# Voltage_Regulation.net
KiCad netlist of a schematic drawn in Altium Designer
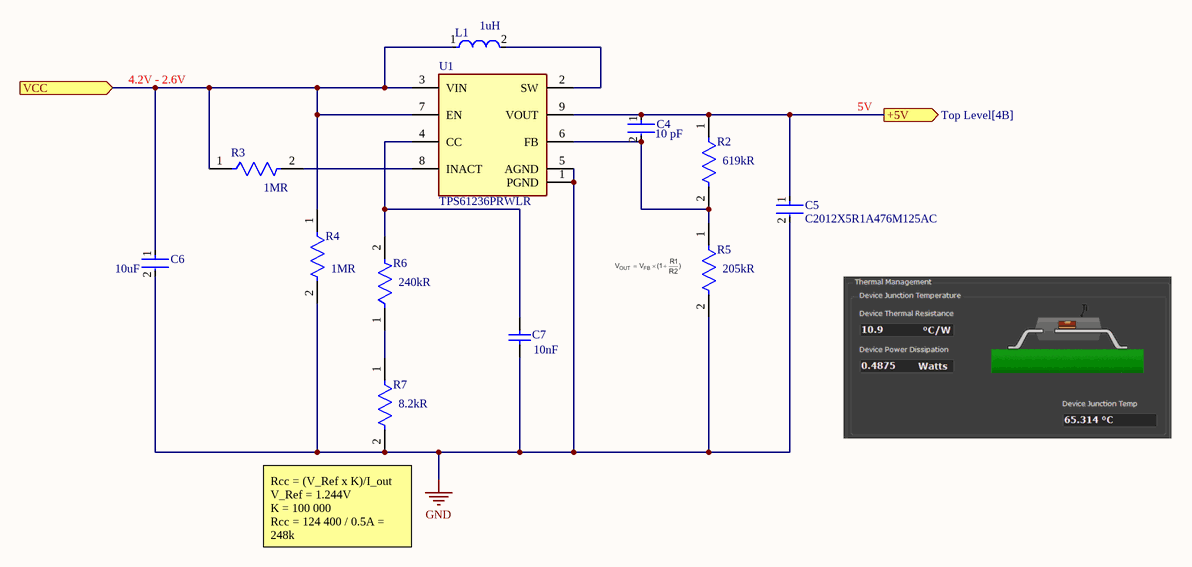
[diagram p0: Voltage Regulation.SchDoc]

(export (version "E")
  (design (tool "Eeschema 10.0.6"))
  (components
    (comp (ref "C4")
      (value "10 pF")
      (footprint "FP-C0805C-DN-MFG")
      (description "CAP CER 10PF 16V 20% NP0 0805")
      (fields
        (field (name "MANUFACTURER PART NUMBER") "C0805C100M4GACTU")
        (field (name "OCTOPART") "https://octopart.com/c0805c100m4gactu-kemet-16430157")
      )
      (libsource (lib "Altium Content Vault") (part "b4654b650e69147ec39a6b967a45e02"))
    )
    (comp (ref "C5")
      (value "C2012X5R1A476M125AC")
      (footprint "FP-C2012-125-0_2-IPC_B")
      (description "Multilayer Ceramic Capacitors 47μF ±20% 10V X5R SMD 0805")
      (fields (field (name "VOLTAGE") "10V") (field (name "TOLERANCE") "20%"))
      (libsource (lib "Altium Content Vault") (part "b4654b650e69147ec39a6b967a45e02"))
    )
    (comp (ref "C6")
      (value "GRM21BR61E106MA73L")
      (footprint "FP-GRM21B-0_15-IPC_A")
      (description "Chip Multilayer Ceramic Capacitors for General Purpose, 0805, 10uF, X5R, 15%, 20%, 25V")
      (fields (field (name "TOLERANCE") "20%") (field (name "CAPACITANCE") "10uF"))
      (libsource (lib "Altium Content Vault") (part "b4654b650e69147ec39a6b967a45e02"))
    )
    (comp (ref "C7")
      (value "GRM155R61A103KA01D")
      (footprint "CAPC1005X55X25NL05T10")
      (fields (field (name "MANUFACTURER") "Murata") (field (name "CAPACITANCE") "10nF"))
      (libsource (lib "Altium Content Vault") (part "CAP"))
    )
    (comp (ref "L1")
      (value "1286AS-H-1R0M=P2")
      (footprint "FP-DFE201612C-MFG")
      (description "FIXED IND 1UH 2.5A 82 MOHM SMD")
      (fields (field (name "TOLERANCE") "20%") (field (name "INDUCTANCE") "1uH"))
      (libsource (lib "Altium Content Vault") (part "725321dda6339637d4d059423bc1c3c"))
    )
    (comp (ref "R2")
      (value "CRCW0402619KFKED")
      (footprint "FP-CRCW0402-e3-IPC_C")
      (description "RES Thick Film, 619kΩ, 1%, 0.063W, 100ppm/°C, 0402")
      (fields (field (name "TOLERANCE") "1%") (field (name "RESISTANCE") "619kR"))
      (libsource (lib "Altium Content Vault") (part "1029c3af85768c4190bb7ad29bc67b5"))
    )
    (comp (ref "R3")
      (value "CRCW04021M00FKEDC")
      (footprint "FP-CRCW0402-C-e3-MFG")
      (description "RES 1M OHM 1% 1/16W 0402")
      (fields (field (name "TOLERANCE") "1%") (field (name "RESISTANCE") "1MR"))
      (libsource (lib "Altium Content Vault") (part "1029c3af85768c4190bb7ad29bc67b5"))
    )
    (comp (ref "R4")
      (value "CRCW04021M00FKEDC")
      (footprint "FP-CRCW0402-C-e3-MFG")
      (description "RES 1M OHM 1% 1/16W 0402")
      (fields (field (name "TOLERANCE") "1%") (field (name "RESISTANCE") "1MR"))
      (libsource (lib "Altium Content Vault") (part "1029c3af85768c4190bb7ad29bc67b5"))
    )
    (comp (ref "R5")
      (value "AC0402FR-07205KL")
      (footprint "FP-AC0402-MFG")
      (description "RES 205kΩ ±1% 0.063W 0402")
      (fields (field (name "TOLERANCE") "1%") (field (name "RESISTANCE") "205kR"))
      (libsource (lib "Altium Content Vault") (part "1029c3af85768c4190bb7ad29bc67b5"))
    )
    (comp (ref "R6")
      (value "ESR03EZPJ244")
      (footprint "FP-ESR03-MFG")
      (description "240kΩ ±5% 0.25W 0603 Anti-Surge Chip Resistor AEC-Q200")
      (fields (field (name "TOLERANCE") "5%") (field (name "RESISTANCE") "240kR"))
      (libsource (lib "Altium Content Vault") (part "1029c3af85768c4190bb7ad29bc67b5"))
    )
    (comp (ref "R7")
      (value "CRCW20108K20JNEF")
      (footprint "FP-CRCW2010-e3-IPC_C")
      (description "RES Thick Film, 8.2kΩ, 5%, 0.75W, 200ppm/°C, 2010")
      (fields (field (name "RESISTANCE") "8.2kR") (field (name "TOLERANCE") "5%"))
      (libsource (lib "Altium Content Vault") (part "1029c3af85768c4190bb7ad29bc67b5"))
    )
    (comp (ref "U1")
      (value "TPS61236PRWLR")
      (footprint "SamacSys:TPS61235PRWLT")
      (description "Integrated Circuit")
      (fields (field (name "MOUSER PART NUMBER") "595-TPS61236PRWLR"))
      (libsource (lib "SamacSys") (part "TPS61236PRWLR"))
    )
  )
  (nets
    (net (code "1") (name "/+5V") (class "Default")
      (node (ref "C4") (pin "1") (pinfunction "1_1") (pintype "passive"))
      (node (ref "C5") (pin "1") (pinfunction "1_1") (pintype "passive"))
      (node (ref "R2") (pin "1") (pinfunction "1_1") (pintype "passive"))
      (node (ref "U1") (pin "9") (pinfunction "VOUT_9") (pintype "passive"))
    )
    (net (code "2") (name "/VCC") (class "Default")
      (node (ref "C6") (pin "1") (pinfunction "1_1") (pintype "passive"))
      (node (ref "L1") (pin "1") (pinfunction "1_1") (pintype "passive"))
      (node (ref "R3") (pin "1") (pinfunction "1_1") (pintype "passive"))
      (node (ref "R4") (pin "1") (pinfunction "1_1") (pintype "passive"))
      (node (ref "U1") (pin "3") (pinfunction "VIN_3") (pintype "passive"))
      (node (ref "U1") (pin "7") (pinfunction "EN_7") (pintype "passive"))
    )
    (net (code "3") (name "GND") (class "Default")
      (node (ref "C5") (pin "2") (pinfunction "2_2") (pintype "passive"))
      (node (ref "C6") (pin "2") (pinfunction "2_2") (pintype "passive"))
      (node (ref "C7") (pin "2") (pinfunction "2_2") (pintype "passive"))
      (node (ref "R4") (pin "2") (pinfunction "2_2") (pintype "passive"))
      (node (ref "R5") (pin "2") (pinfunction "2_2") (pintype "passive"))
      (node (ref "R7") (pin "2") (pinfunction "2_2") (pintype "passive"))
      (node (ref "U1") (pin "1") (pinfunction "PGND_1") (pintype "passive"))
      (node (ref "U1") (pin "5") (pinfunction "AGND_5") (pintype "passive"))
    )
    (net (code "4") (name "Net-(R6-Pad1)") (class "Default")
      (node (ref "R6") (pin "1") (pinfunction "1_1") (pintype "passive"))
      (node (ref "R7") (pin "1") (pinfunction "1_1") (pintype "passive"))
    )
    (net (code "5") (name "Net-(U1-CC)") (class "Default")
      (node (ref "C7") (pin "1") (pinfunction "1_1") (pintype "passive"))
      (node (ref "R6") (pin "2") (pinfunction "2_2") (pintype "passive"))
      (node (ref "U1") (pin "4") (pinfunction "CC_4") (pintype "passive"))
    )
    (net (code "6") (name "Net-(U1-FB)") (class "Default")
      (node (ref "C4") (pin "2") (pinfunction "2_2") (pintype "passive"))
      (node (ref "R2") (pin "2") (pinfunction "2_2") (pintype "passive"))
      (node (ref "R5") (pin "1") (pinfunction "1_1") (pintype "passive"))
      (node (ref "U1") (pin "6") (pinfunction "FB_6") (pintype "passive"))
    )
    (net (code "7") (name "Net-(U1-INACT)") (class "Default")
      (node (ref "R3") (pin "2") (pinfunction "2_2") (pintype "passive"))
      (node (ref "U1") (pin "8") (pinfunction "INACT_8") (pintype "passive"))
    )
    (net (code "8") (name "Net-(U1-SW)") (class "Default")
      (node (ref "L1") (pin "2") (pinfunction "2_2") (pintype "passive"))
      (node (ref "U1") (pin "2") (pinfunction "SW_2") (pintype "passive"))
    )
  )
)
